# UKU208_cpu.net
KiCad netlist of a schematic drawn in Altium Designer
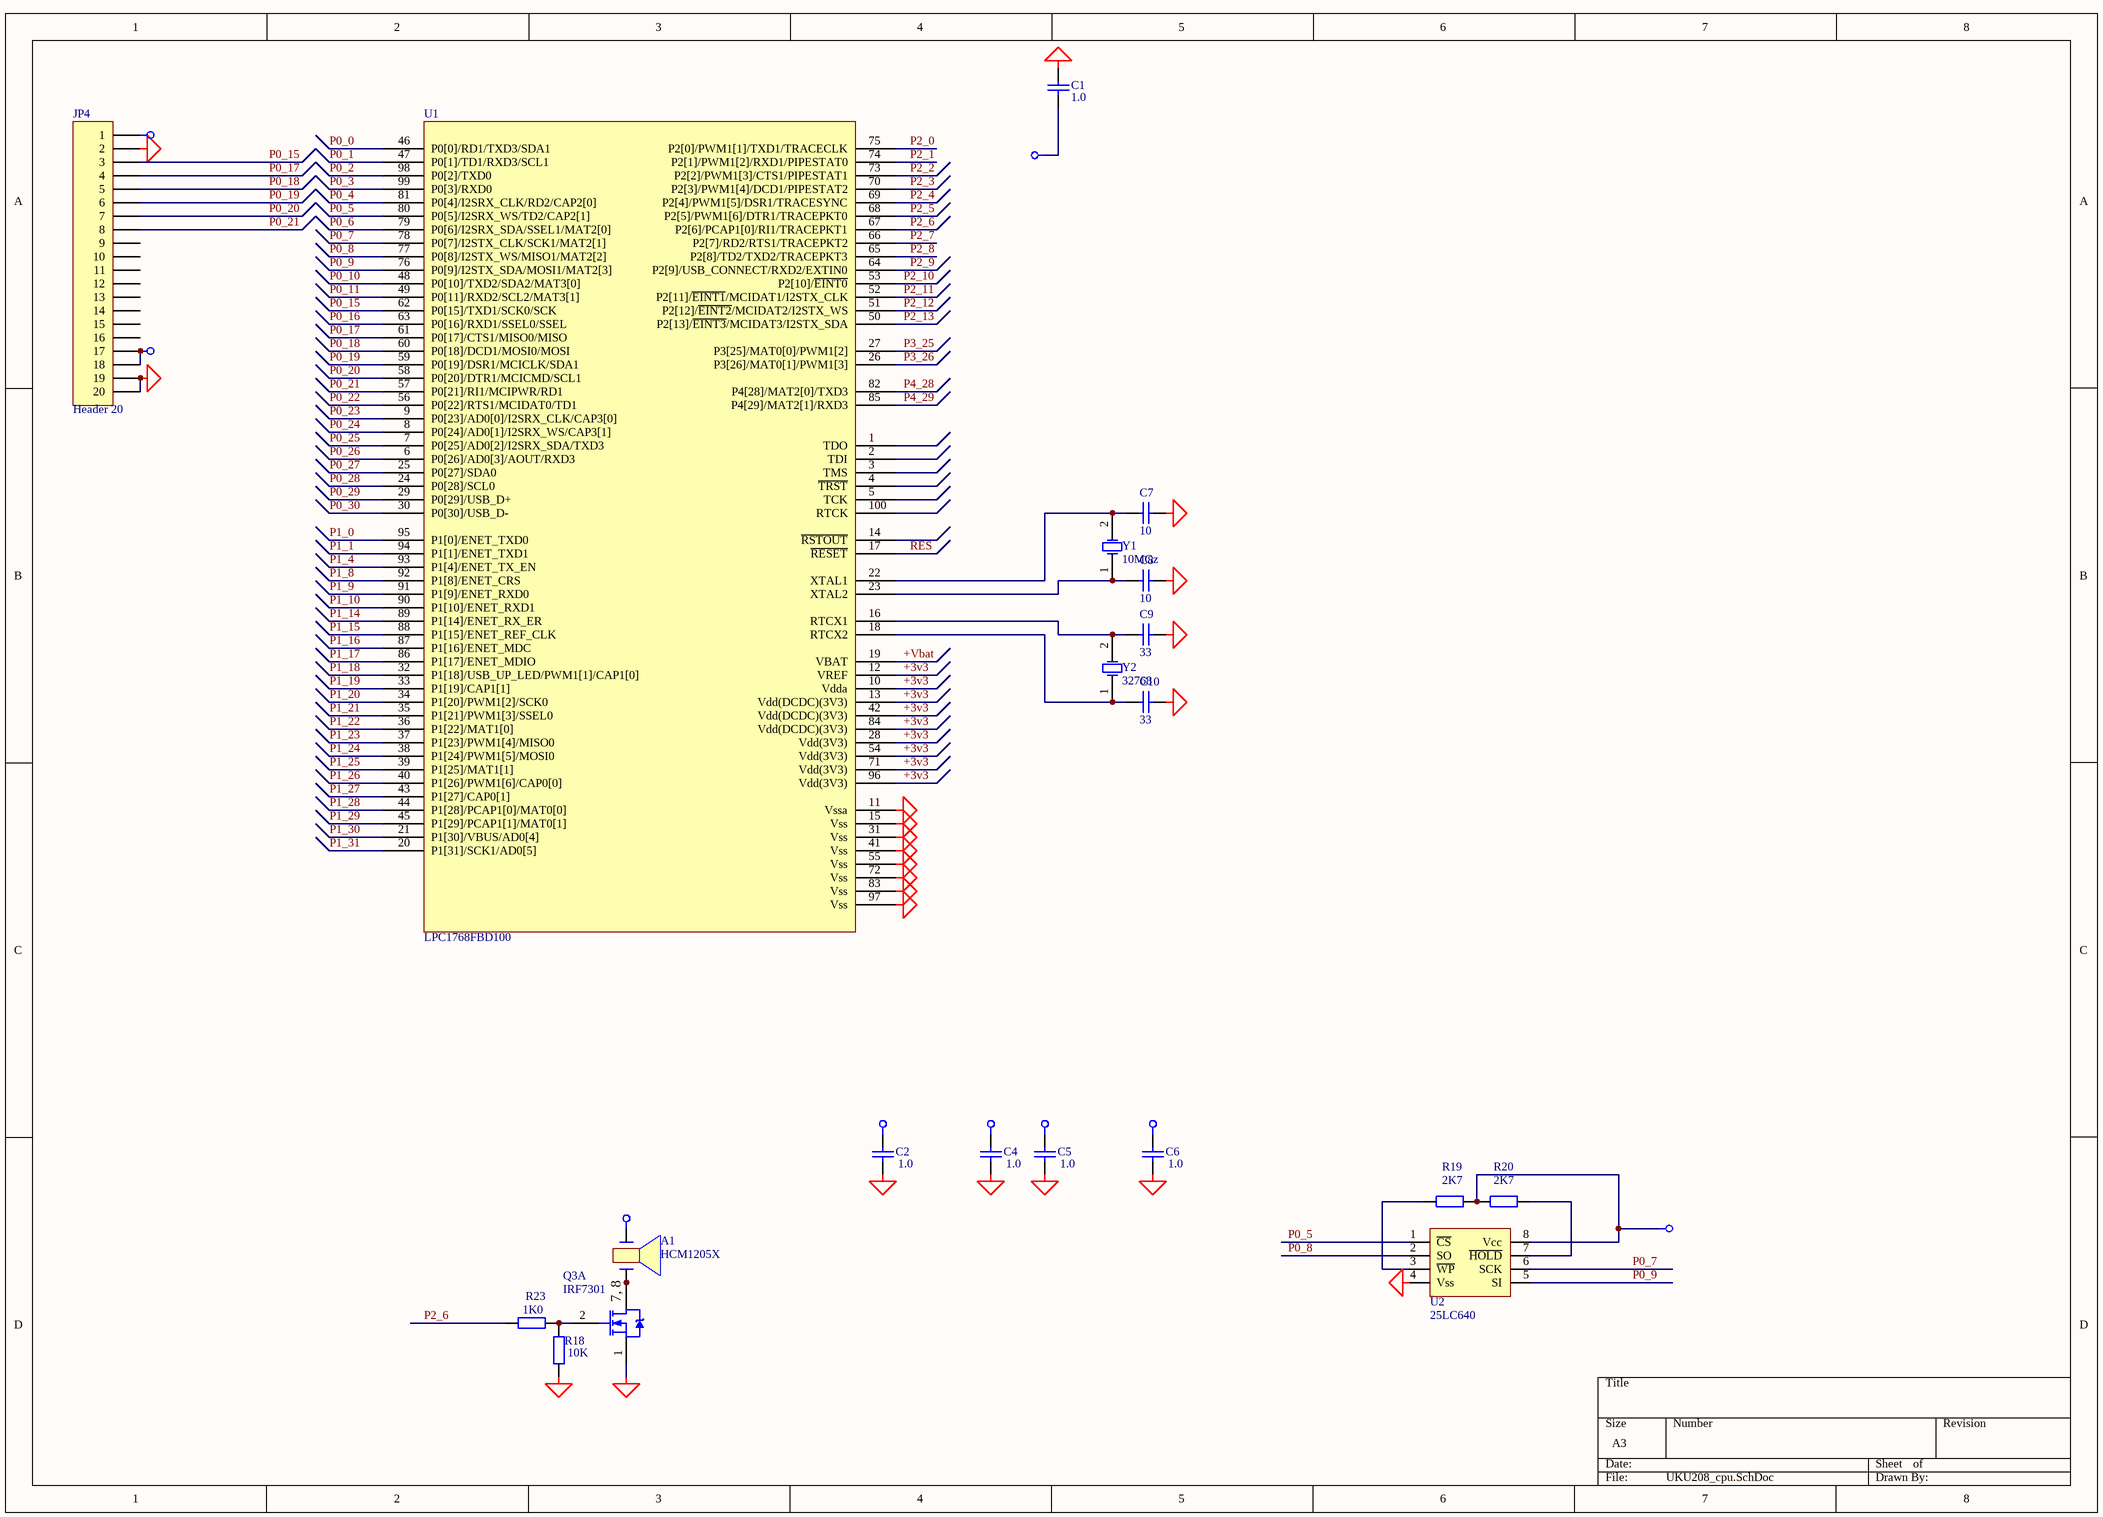
[diagram p0: UKU208_cpu.SchDoc]

(export (version "E")
  (design (tool "Eeschema 10.0.6"))
  (components
    (comp (ref "A1")
      (value "HCM1205X")
      (footprint "zumm")
      (description "Beeper")
      (libsource (lib "PAL") (part "PJEZ0"))
    )
    (comp (ref "C1")
      (value "1.0")
      (footprint "_1206")
      (description "Capacitor")
      (fields (field (name "MANUFACTURER") "Generic Components") (field (name "PUBLISHER") "Altium Limited"))
      (libsource (lib "Miscellaneous Devices") (part "Cap Semi"))
    )
    (comp (ref "C2")
      (value "1.0")
      (footprint "_1206")
      (description "Capacitor")
      (fields (field (name "MANUFACTURER") "Generic Components") (field (name "PUBLISHER") "Altium Limited"))
      (libsource (lib "Miscellaneous Devices") (part "Cap Semi"))
    )
    (comp (ref "C4")
      (value "1.0")
      (footprint "_1206")
      (description "Capacitor")
      (fields (field (name "MANUFACTURER") "Generic Components") (field (name "PUBLISHER") "Altium Limited"))
      (libsource (lib "Miscellaneous Devices") (part "Cap Semi"))
    )
    (comp (ref "C5")
      (value "1.0")
      (footprint "_1206")
      (description "Capacitor")
      (fields (field (name "MANUFACTURER") "Generic Components") (field (name "PUBLISHER") "Altium Limited"))
      (libsource (lib "Miscellaneous Devices") (part "Cap Semi"))
    )
    (comp (ref "C6")
      (value "1.0")
      (footprint "_1206")
      (description "Capacitor")
      (fields (field (name "MANUFACTURER") "Generic Components") (field (name "PUBLISHER") "Altium Limited"))
      (libsource (lib "Miscellaneous Devices") (part "Cap Semi"))
    )
    (comp (ref "C7")
      (value "10")
      (footprint "_1206")
      (description "Capacitor")
      (fields (field (name "MANUFACTURER") "Generic Components") (field (name "PUBLISHER") "Altium Limited"))
      (libsource (lib "Miscellaneous Devices") (part "Cap Semi"))
    )
    (comp (ref "C8")
      (value "10")
      (footprint "_1206")
      (description "Capacitor")
      (fields (field (name "MANUFACTURER") "Generic Components") (field (name "PUBLISHER") "Altium Limited"))
      (libsource (lib "Miscellaneous Devices") (part "Cap Semi"))
    )
    (comp (ref "C9")
      (value "33")
      (footprint "_1206")
      (description "Capacitor (Semiconductor SIM Model)")
      (fields (field (name "MANUFACTURER") "Generic Components") (field (name "PUBLISHER") "Altium Limited"))
      (libsource (lib "Miscellaneous Devices") (part "Cap Semi"))
    )
    (comp (ref "C10")
      (value "33")
      (footprint "_1206")
      (description "Capacitor (Semiconductor SIM Model)")
      (fields (field (name "MANUFACTURER") "Generic Components") (field (name "PUBLISHER") "Altium Limited"))
      (libsource (lib "Miscellaneous Devices") (part "Cap Semi"))
    )
    (comp (ref "JP4")
      (value "Header 20")
      (footprint "XF2M20151A")
      (description "Header, 20-Pin")
      (fields (field (name "MANUFACTURER") "Generic Components") (field (name "PUBLISHER") "Altium Limited"))
      (libsource (lib "Miscellaneous Connectors") (part "Header 20"))
    )
    (comp (ref "Q3")
      (value "IRF7301")
      (footprint "SO-G8/Y2.2")
      (description "FET")
      (fields
        (field (name "MANUFACTURER") "International Rectifier")
        (field (name "PUBLISHER") "Altium Limited")
      )
      (libsource (lib "IR Discrete MOSFET") (part "IRF7301"))
    )
    (comp (ref "R18")
      (value "10K")
      (footprint "_1206")
      (description "Resistor")
      (fields (field (name "MANUFACTURER") "Generic Components") (field (name "PUBLISHER") "Altium Limited"))
      (libsource (lib "Miscellaneous Devices") (part "Res2"))
    )
    (comp (ref "R19")
      (value "2K7")
      (footprint "_1206")
      (description "Resistor")
      (fields (field (name "MANUFACTURER") "Generic Components") (field (name "PUBLISHER") "Altium Limited"))
      (libsource (lib "") (part "Res2_1"))
    )
    (comp (ref "R20")
      (value "2K7")
      (footprint "_1206")
      (description "Resistor")
      (fields (field (name "MANUFACTURER") "Generic Components") (field (name "PUBLISHER") "Altium Limited"))
      (libsource (lib "") (part "Res2_1"))
    )
    (comp (ref "R23")
      (value "1K0")
      (footprint "_1206")
      (description "Resistor")
      (fields (field (name "MANUFACTURER") "Generic Components") (field (name "PUBLISHER") "Altium Limited"))
      (libsource (lib "") (part "Res2_1"))
    )
    (comp (ref "U1")
      (value "LPC1768FBD100")
      (footprint "LPC2368")
      (libsource (lib "PAL") (part "LPC2368FBD100"))
    )
    (comp (ref "U2")
      (value "25LC640")
      (footprint "SO-G8/D5")
      (description "Memory")
      (libsource (lib "PAL") (part "25LC640"))
    )
    (comp (ref "Y1")
      (value "10MGz")
      (footprint "QWARZ1")
      (description "Crystal Oscillator")
      (fields (field (name "MANUFACTURER") "Generic Components") (field (name "PUBLISHER") "Altium Limited"))
      (libsource (lib "Miscellaneous Devices") (part "XTAL"))
    )
    (comp (ref "Y2")
      (value "32768")
      (footprint "QWARZ2")
      (description "Crystal Oscillator")
      (fields (field (name "MANUFACTURER") "Generic Components") (field (name "PUBLISHER") "Altium Limited"))
      (libsource (lib "Miscellaneous Devices") (part "XTAL"))
    )
  )
  (nets
    (net (code "1") (name "+3v3") (class "Default")
      (node (ref "C1") (pin "1") (pinfunction "1_1") (pintype "passive"))
      (node (ref "C5") (pin "2") (pinfunction "2_2") (pintype "passive"))
      (node (ref "JP4") (pin "1") (pinfunction "1_1") (pintype "passive"))
      (node (ref "U1") (pin "10") (pinfunction "Vdda_10") (pintype "passive"))
      (node (ref "U1") (pin "12") (pinfunction "VREF_12") (pintype "passive"))
      (node (ref "U1") (pin "13") (pinfunction "Vdd(DCDC)(3V3)_13") (pintype "passive"))
      (node (ref "U1") (pin "28") (pinfunction "Vdd(3V3)_28") (pintype "passive"))
      (node (ref "U1") (pin "42") (pinfunction "Vdd(DCDC)(3V3)_42") (pintype "passive"))
      (node (ref "U1") (pin "54") (pinfunction "Vdd(3V3)_54") (pintype "passive"))
      (node (ref "U1") (pin "71") (pinfunction "Vdd(3V3)_71") (pintype "passive"))
      (node (ref "U1") (pin "84") (pinfunction "Vdd(DCDC)(3V3)_84") (pintype "passive"))
      (node (ref "U1") (pin "96") (pinfunction "Vdd(3V3)_96") (pintype "passive"))
    )
    (net (code "2") (name "+5v") (class "Default")
      (node (ref "A1") (pin "1") (pinfunction "1_1") (pintype "passive"))
      (node (ref "C2") (pin "2") (pinfunction "2_2") (pintype "passive"))
      (node (ref "C4") (pin "2") (pinfunction "2_2") (pintype "passive"))
      (node (ref "C6") (pin "2") (pinfunction "2_2") (pintype "passive"))
      (node (ref "JP4") (pin "17") (pinfunction "17_17") (pintype "passive"))
      (node (ref "JP4") (pin "18") (pinfunction "18_18") (pintype "passive"))
      (node (ref "R19") (pin "2") (pinfunction "2_2") (pintype "passive"))
      (node (ref "R20") (pin "1") (pinfunction "1_1") (pintype "passive"))
      (node (ref "U2") (pin "8") (pinfunction "Vcc_8") (pintype "passive"))
    )
    (net (code "3") (name "/+Vbat") (class "Default")
      (node (ref "U1") (pin "19") (pinfunction "VBAT_19") (pintype "passive"))
    )
    (net (code "4") (name "/P0_0") (class "Default")
      (node (ref "U1") (pin "46") (pinfunction "P0[0]/RD1/TXD3/SDA1_46") (pintype "passive"))
    )
    (net (code "5") (name "/P0_1") (class "Default")
      (node (ref "U1") (pin "47") (pinfunction "P0[1]/TD1/RXD3/SCL1_47") (pintype "passive"))
    )
    (net (code "6") (name "/P0_2") (class "Default")
      (node (ref "U1") (pin "98") (pinfunction "P0[2]/TXD0_98") (pintype "passive"))
    )
    (net (code "7") (name "/P0_3") (class "Default")
      (node (ref "U1") (pin "99") (pinfunction "P0[3]/RXD0_99") (pintype "passive"))
    )
    (net (code "8") (name "/P0_4") (class "Default")
      (node (ref "U1") (pin "81") (pinfunction "P0[4]/I2SRX_CLK/RD2/CAP2[0]_81") (pintype "passive"))
    )
    (net (code "9") (name "/P0_5") (class "Default")
      (node (ref "U1") (pin "80") (pinfunction "P0[5]/I2SRX_WS/TD2/CAP2[1]_80") (pintype "passive"))
      (node (ref "U2") (pin "1") (pinfunction "~{CS}_1") (pintype "passive"))
    )
    (net (code "10") (name "/P0_6") (class "Default")
      (node (ref "U1") (pin "79") (pinfunction "P0[6]/I2SRX_SDA/SSEL1/MAT2[0]_79") (pintype "passive"))
    )
    (net (code "11") (name "/P0_7") (class "Default")
      (node (ref "U1") (pin "78") (pinfunction "P0[7]/I2STX_CLK/SCK1/MAT2[1]_78") (pintype "passive"))
      (node (ref "U2") (pin "6") (pinfunction "SCK_6") (pintype "passive"))
    )
    (net (code "12") (name "/P0_8") (class "Default")
      (node (ref "U1") (pin "77") (pinfunction "P0[8]/I2STX_WS/MISO1/MAT2[2]_77") (pintype "passive"))
      (node (ref "U2") (pin "2") (pinfunction "SO_2") (pintype "passive"))
    )
    (net (code "13") (name "/P0_9") (class "Default")
      (node (ref "U1") (pin "76") (pinfunction "P0[9]/I2STX_SDA/MOSI1/MAT2[3]_76") (pintype "passive"))
      (node (ref "U2") (pin "5") (pinfunction "SI_5") (pintype "passive"))
    )
    (net (code "14") (name "/P0_10") (class "Default")
      (node (ref "U1") (pin "48") (pinfunction "P0[10]/TXD2/SDA2/MAT3[0]_48") (pintype "passive"))
    )
    (net (code "15") (name "/P0_11") (class "Default")
      (node (ref "U1") (pin "49") (pinfunction "P0[11]/RXD2/SCL2/MAT3[1]_49") (pintype "passive"))
    )
    (net (code "16") (name "/P0_15") (class "Default")
      (node (ref "JP4") (pin "3") (pinfunction "3_3") (pintype "passive"))
      (node (ref "U1") (pin "62") (pinfunction "P0[15]/TXD1/SCK0/SCK_62") (pintype "passive"))
    )
    (net (code "17") (name "/P0_16") (class "Default")
      (node (ref "U1") (pin "63") (pinfunction "P0[16]/RXD1/SSEL0/SSEL_63") (pintype "passive"))
    )
    (net (code "18") (name "/P0_17") (class "Default")
      (node (ref "JP4") (pin "4") (pinfunction "4_4") (pintype "passive"))
      (node (ref "U1") (pin "61") (pinfunction "P0[17]/CTS1/MISO0/MISO_61") (pintype "passive"))
    )
    (net (code "19") (name "/P0_18") (class "Default")
      (node (ref "JP4") (pin "5") (pinfunction "5_5") (pintype "passive"))
      (node (ref "U1") (pin "60") (pinfunction "P0[18]/DCD1/MOSI0/MOSI_60") (pintype "passive"))
    )
    (net (code "20") (name "/P0_19") (class "Default")
      (node (ref "JP4") (pin "6") (pinfunction "6_6") (pintype "passive"))
      (node (ref "U1") (pin "59") (pinfunction "P0[19]/DSR1/MCICLK/SDA1_59") (pintype "passive"))
    )
    (net (code "21") (name "/P0_20") (class "Default")
      (node (ref "JP4") (pin "7") (pinfunction "7_7") (pintype "passive"))
      (node (ref "U1") (pin "58") (pinfunction "P0[20]/DTR1/MCICMD/SCL1_58") (pintype "passive"))
    )
    (net (code "22") (name "/P0_21") (class "Default")
      (node (ref "JP4") (pin "8") (pinfunction "8_8") (pintype "passive"))
      (node (ref "U1") (pin "57") (pinfunction "P0[21]/RI1/MCIPWR/RD1_57") (pintype "passive"))
    )
    (net (code "23") (name "/P0_22") (class "Default")
      (node (ref "U1") (pin "56") (pinfunction "P0[22]/RTS1/MCIDAT0/TD1_56") (pintype "passive"))
    )
    (net (code "24") (name "/P0_23") (class "Default")
      (node (ref "U1") (pin "9") (pinfunction "P0[23]/AD0[0]/I2SRX_CLK/CAP3[0]_9") (pintype "passive"))
    )
    (net (code "25") (name "/P0_24") (class "Default")
      (node (ref "U1") (pin "8") (pinfunction "P0[24]/AD0[1]/I2SRX_WS/CAP3[1]_8") (pintype "passive"))
    )
    (net (code "26") (name "/P0_25") (class "Default")
      (node (ref "U1") (pin "7") (pinfunction "P0[25]/AD0[2]/I2SRX_SDA/TXD3_7") (pintype "passive"))
    )
    (net (code "27") (name "/P0_26") (class "Default")
      (node (ref "U1") (pin "6") (pinfunction "P0[26]/AD0[3]/AOUT/RXD3_6") (pintype "passive"))
    )
    (net (code "28") (name "/P0_27") (class "Default")
      (node (ref "U1") (pin "25") (pinfunction "P0[27]/SDA0_25") (pintype "passive"))
    )
    (net (code "29") (name "/P0_28") (class "Default")
      (node (ref "U1") (pin "24") (pinfunction "P0[28]/SCL0_24") (pintype "passive"))
    )
    (net (code "30") (name "/P0_29") (class "Default")
      (node (ref "U1") (pin "29") (pinfunction "P0[29]/USB_D+_29") (pintype "passive"))
    )
    (net (code "31") (name "/P0_30") (class "Default")
      (node (ref "U1") (pin "30") (pinfunction "P0[30]/USB_D-_30") (pintype "passive"))
    )
    (net (code "32") (name "/P1_0") (class "Default")
      (node (ref "U1") (pin "95") (pinfunction "P1[0]/ENET_TXD0_95") (pintype "passive"))
    )
    (net (code "33") (name "/P1_1") (class "Default")
      (node (ref "U1") (pin "94") (pinfunction "P1[1]/ENET_TXD1_94") (pintype "passive"))
    )
    (net (code "34") (name "/P1_4") (class "Default")
      (node (ref "U1") (pin "93") (pinfunction "P1[4]/ENET_TX_EN_93") (pintype "passive"))
    )
    (net (code "35") (name "/P1_8") (class "Default")
      (node (ref "U1") (pin "92") (pinfunction "P1[8]/ENET_CRS_92") (pintype "passive"))
    )
    (net (code "36") (name "/P1_9") (class "Default")
      (node (ref "U1") (pin "91") (pinfunction "P1[9]/ENET_RXD0_91") (pintype "passive"))
    )
    (net (code "37") (name "/P1_10") (class "Default")
      (node (ref "U1") (pin "90") (pinfunction "P1[10]/ENET_RXD1_90") (pintype "passive"))
    )
    (net (code "38") (name "/P1_14") (class "Default")
      (node (ref "U1") (pin "89") (pinfunction "P1[14]/ENET_RX_ER_89") (pintype "passive"))
    )
    (net (code "39") (name "/P1_15") (class "Default")
      (node (ref "U1") (pin "88") (pinfunction "P1[15]/ENET_REF_CLK_88") (pintype "passive"))
    )
    (net (code "40") (name "/P1_16") (class "Default")
      (node (ref "U1") (pin "87") (pinfunction "P1[16]/ENET_MDC_87") (pintype "passive"))
    )
    (net (code "41") (name "/P1_17") (class "Default")
      (node (ref "U1") (pin "86") (pinfunction "P1[17]/ENET_MDIO_86") (pintype "passive"))
    )
    (net (code "42") (name "/P1_18") (class "Default")
      (node (ref "U1") (pin "32") (pinfunction "P1[18]/USB_UP_LED/PWM1[1]/CAP1[0]_32") (pintype "passive"))
    )
    (net (code "43") (name "/P1_19") (class "Default")
      (node (ref "U1") (pin "33") (pinfunction "P1[19]/CAP1[1]_33") (pintype "passive"))
    )
    (net (code "44") (name "/P1_20") (class "Default")
      (node (ref "U1") (pin "34") (pinfunction "P1[20]/PWM1[2]/SCK0_34") (pintype "passive"))
    )
    (net (code "45") (name "/P1_21") (class "Default")
      (node (ref "U1") (pin "35") (pinfunction "P1[21]/PWM1[3]/SSEL0_35") (pintype "passive"))
    )
    (net (code "46") (name "/P1_22") (class "Default")
      (node (ref "U1") (pin "36") (pinfunction "P1[22]/MAT1[0]_36") (pintype "passive"))
    )
    (net (code "47") (name "/P1_23") (class "Default")
      (node (ref "U1") (pin "37") (pinfunction "P1[23]/PWM1[4]/MISO0_37") (pintype "passive"))
    )
    (net (code "48") (name "/P1_24") (class "Default")
      (node (ref "U1") (pin "38") (pinfunction "P1[24]/PWM1[5]/MOSI0_38") (pintype "passive"))
    )
    (net (code "49") (name "/P1_25") (class "Default")
      (node (ref "U1") (pin "39") (pinfunction "P1[25]/MAT1[1]_39") (pintype "passive"))
    )
    (net (code "50") (name "/P1_26") (class "Default")
      (node (ref "U1") (pin "40") (pinfunction "P1[26]/PWM1[6]/CAP0[0]_40") (pintype "passive"))
    )
    (net (code "51") (name "/P1_27") (class "Default")
      (node (ref "U1") (pin "43") (pinfunction "P1[27]/CAP0[1]_43") (pintype "passive"))
    )
    (net (code "52") (name "/P1_28") (class "Default")
      (node (ref "U1") (pin "44") (pinfunction "P1[28]/PCAP1[0]/MAT0[0]_44") (pintype "passive"))
    )
    (net (code "53") (name "/P1_29") (class "Default")
      (node (ref "U1") (pin "45") (pinfunction "P1[29]/PCAP1[1]/MAT0[1]_45") (pintype "passive"))
    )
    (net (code "54") (name "/P1_30") (class "Default")
      (node (ref "U1") (pin "21") (pinfunction "P1[30]/VBUS/AD0[4]_21") (pintype "passive"))
    )
    (net (code "55") (name "/P1_31") (class "Default")
      (node (ref "U1") (pin "20") (pinfunction "P1[31]/SCK1/AD0[5]_20") (pintype "passive"))
    )
    (net (code "56") (name "/P2_0") (class "Default")
      (node (ref "U1") (pin "75") (pinfunction "P2[0]/PWM1[1]/TXD1/TRACECLK_75") (pintype "passive"))
    )
    (net (code "57") (name "/P2_1") (class "Default")
      (node (ref "U1") (pin "74") (pinfunction "P2[1]/PWM1[2]/RXD1/PIPESTAT0_74") (pintype "passive"))
    )
    (net (code "58") (name "/P2_2") (class "Default")
      (node (ref "U1") (pin "73") (pinfunction "P2[2]/PWM1[3]/CTS1/PIPESTAT1_73") (pintype "passive"))
    )
    (net (code "59") (name "/P2_3") (class "Default")
      (node (ref "U1") (pin "70") (pinfunction "P2[3]/PWM1[4]/DCD1/PIPESTAT2_70") (pintype "passive"))
    )
    (net (code "60") (name "/P2_4") (class "Default")
      (node (ref "U1") (pin "69") (pinfunction "P2[4]/PWM1[5]/DSR1/TRACESYNC_69") (pintype "passive"))
    )
    (net (code "61") (name "/P2_5") (class "Default")
      (node (ref "U1") (pin "68") (pinfunction "P2[5]/PWM1[6]/DTR1/TRACEPKT0_68") (pintype "passive"))
    )
    (net (code "62") (name "/P2_6") (class "Default")
      (node (ref "R23") (pin "1") (pinfunction "1_1") (pintype "passive"))
      (node (ref "U1") (pin "67") (pinfunction "P2[6]/PCAP1[0]/RI1/TRACEPKT1_67") (pintype "passive"))
    )
    (net (code "63") (name "/P2_7") (class "Default")
      (node (ref "U1") (pin "66") (pinfunction "P2[7]/RD2/RTS1/TRACEPKT2_66") (pintype "passive"))
    )
    (net (code "64") (name "/P2_8") (class "Default")
      (node (ref "U1") (pin "65") (pinfunction "P2[8]/TD2/TXD2/TRACEPKT3_65") (pintype "passive"))
    )
    (net (code "65") (name "/P2_9") (class "Default")
      (node (ref "U1") (pin "64") (pinfunction "P2[9]/USB_CONNECT/RXD2/EXTIN0_64") (pintype "passive"))
    )
    (net (code "66") (name "/P2_10") (class "Default")
      (node (ref "U1") (pin "53") (pinfunction "P2[10]/~{EINT0}_53") (pintype "passive"))
    )
    (net (code "67") (name "/P2_11") (class "Default")
      (node (ref "U1") (pin "52") (pinfunction "P2[11]/~{EINT1}/MCIDAT1/I2STX_CLK_52") (pintype "passive"))
    )
    (net (code "68") (name "/P2_12") (class "Default")
      (node (ref "U1") (pin "51") (pinfunction "P2[12]/~{EINT2}/MCIDAT2/I2STX_WS_51") (pintype "passive"))
    )
    (net (code "69") (name "/P2_13") (class "Default")
      (node (ref "U1") (pin "50") (pinfunction "P2[13]/~{EINT3}/MCIDAT3/I2STX_SDA_50") (pintype "passive"))
    )
    (net (code "70") (name "/P3_25") (class "Default")
      (node (ref "U1") (pin "27") (pinfunction "P3[25]/MAT0[0]/PWM1[2]_27") (pintype "passive"))
    )
    (net (code "71") (name "/P3_26") (class "Default")
      (node (ref "U1") (pin "26") (pinfunction "P3[26]/MAT0[1]/PWM1[3]_26") (pintype "passive"))
    )
    (net (code "72") (name "/P4_28") (class "Default")
      (node (ref "U1") (pin "82") (pinfunction "P4[28]/MAT2[0]/TXD3_82") (pintype "passive"))
    )
    (net (code "73") (name "/P4_29") (class "Default")
      (node (ref "U1") (pin "85") (pinfunction "P4[29]/MAT2[1]/RXD3_85") (pintype "passive"))
    )
    (net (code "74") (name "/RES") (class "Default")
      (node (ref "U1") (pin "17") (pinfunction "~{RESET}_17") (pintype "passive"))
    )
    (net (code "75") (name "GND") (class "Default")
      (node (ref "C1") (pin "2") (pinfunction "2_2") (pintype "passive"))
      (node (ref "C10") (pin "1") (pinfunction "1_1") (pintype "passive"))
      (node (ref "C2") (pin "1") (pinfunction "1_1") (pintype "passive"))
      (node (ref "C4") (pin "1") (pinfunction "1_1") (pintype "passive"))
      (node (ref "C5") (pin "1") (pinfunction "1_1") (pintype "passive"))
      (node (ref "C6") (pin "1") (pinfunction "1_1") (pintype "passive"))
      (node (ref "C7") (pin "1") (pinfunction "1_1") (pintype "passive"))
      (node (ref "C8") (pin "1") (pinfunction "1_1") (pintype "passive"))
      (node (ref "C9") (pin "1") (pinfunction "1_1") (pintype "passive"))
      (node (ref "JP4") (pin "19") (pinfunction "19_19") (pintype "passive"))
      (node (ref "JP4") (pin "2") (pinfunction "2_2") (pintype "passive"))
      (node (ref "JP4") (pin "20") (pinfunction "20_20") (pintype "passive"))
      (node (ref "Q3") (pin "1") (pinfunction "S_1") (pintype "passive"))
      (node (ref "R18") (pin "1") (pinfunction "1_1") (pintype "passive"))
      (node (ref "U1") (pin "11") (pinfunction "Vssa_11") (pintype "passive"))
      (node (ref "U1") (pin "15") (pinfunction "Vss_15") (pintype "passive"))
      (node (ref "U1") (pin "31") (pinfunction "Vss_31") (pintype "passive"))
      (node (ref "U1") (pin "41") (pinfunction "Vss_41") (pintype "passive"))
      (node (ref "U1") (pin "55") (pinfunction "Vss_55") (pintype "passive"))
      (node (ref "U1") (pin "72") (pinfunction "Vss_72") (pintype "passive"))
      (node (ref "U1") (pin "83") (pinfunction "Vss_83") (pintype "passive"))
      (node (ref "U1") (pin "97") (pinfunction "Vss_97") (pintype "passive"))
      (node (ref "U2") (pin "4") (pinfunction "Vss_4") (pintype "passive"))
    )
    (net (code "76") (name "Net-(A1-Pad2)") (class "Default")
      (node (ref "A1") (pin "2") (pinfunction "2_2") (pintype "passive"))
      (node (ref "Q3") (pin "7") (pinfunction "D_7") (pintype "passive"))
      (node (ref "Q3") (pin "8") (pinfunction "D_8") (pintype "passive"))
    )
    (net (code "77") (name "Net-(Q3A-G)") (class "Default")
      (node (ref "Q3") (pin "2") (pinfunction "G_2") (pintype "passive"))
      (node (ref "R18") (pin "2") (pinfunction "2_2") (pintype "passive"))
      (node (ref "R23") (pin "2") (pinfunction "2_2") (pintype "passive"))
    )
    (net (code "78") (name "Net-(U1-RTCX1)") (class "Default")
      (node (ref "C9") (pin "2") (pinfunction "2_2") (pintype "passive"))
      (node (ref "U1") (pin "16") (pinfunction "RTCX1_16") (pintype "passive"))
      (node (ref "Y2") (pin "2") (pinfunction "OSC2_2") (pintype "passive"))
    )
    (net (code "79") (name "Net-(U1-RTCX2)") (class "Default")
      (node (ref "C10") (pin "2") (pinfunction "2_2") (pintype "passive"))
      (node (ref "U1") (pin "18") (pinfunction "RTCX2_18") (pintype "passive"))
      (node (ref "Y2") (pin "1") (pinfunction "OSC1_1") (pintype "passive"))
    )
    (net (code "80") (name "Net-(U1-XTAL1)") (class "Default")
      (node (ref "C7") (pin "2") (pinfunction "2_2") (pintype "passive"))
      (node (ref "U1") (pin "22") (pinfunction "XTAL1_22") (pintype "passive"))
      (node (ref "Y1") (pin "2") (pinfunction "OSC2_2") (pintype "passive"))
    )
    (net (code "81") (name "Net-(U1-XTAL2)") (class "Default")
      (node (ref "C8") (pin "2") (pinfunction "2_2") (pintype "passive"))
      (node (ref "U1") (pin "23") (pinfunction "XTAL2_23") (pintype "passive"))
      (node (ref "Y1") (pin "1") (pinfunction "OSC1_1") (pintype "passive"))
    )
    (net (code "82") (name "Net-(U2-~{HOLD})") (class "Default")
      (node (ref "R20") (pin "2") (pinfunction "2_2") (pintype "passive"))
      (node (ref "U2") (pin "7") (pinfunction "~{HOLD}_7") (pintype "passive"))
    )
    (net (code "83") (name "Net-(U2-~{WP})") (class "Default")
      (node (ref "R19") (pin "1") (pinfunction "1_1") (pintype "passive"))
      (node (ref "U2") (pin "3") (pinfunction "~{WP}_3") (pintype "passive"))
    )
    (net (code "84") (name "unconnected-(JP4-Pad9)") (class "Default")
      (node (ref "JP4") (pin "9") (pinfunction "9_9") (pintype "passive"))
    )
    (net (code "85") (name "unconnected-(JP4-Pad10)") (class "Default")
      (node (ref "JP4") (pin "10") (pinfunction "10_10") (pintype "passive"))
    )
    (net (code "86") (name "unconnected-(JP4-Pad11)") (class "Default")
      (node (ref "JP4") (pin "11") (pinfunction "11_11") (pintype "passive"))
    )
    (net (code "87") (name "unconnected-(JP4-Pad12)") (class "Default")
      (node (ref "JP4") (pin "12") (pinfunction "12_12") (pintype "passive"))
    )
    (net (code "88") (name "unconnected-(JP4-Pad13)") (class "Default")
      (node (ref "JP4") (pin "13") (pinfunction "13_13") (pintype "passive"))
    )
    (net (code "89") (name "unconnected-(JP4-Pad14)") (class "Default")
      (node (ref "JP4") (pin "14") (pinfunction "14_14") (pintype "passive"))
    )
    (net (code "90") (name "unconnected-(JP4-Pad15)") (class "Default")
      (node (ref "JP4") (pin "15") (pinfunction "15_15") (pintype "passive"))
    )
    (net (code "91") (name "unconnected-(JP4-Pad16)") (class "Default")
      (node (ref "JP4") (pin "16") (pinfunction "16_16") (pintype "passive"))
    )
    (net (code "92") (name "unconnected-(U1-RTCK-Pad100)") (class "Default")
      (node (ref "U1") (pin "100") (pinfunction "RTCK_100") (pintype "passive"))
    )
    (net (code "93") (name "unconnected-(U1-TCK-Pad5)") (class "Default")
      (node (ref "U1") (pin "5") (pinfunction "TCK_5") (pintype "passive"))
    )
    (net (code "94") (name "unconnected-(U1-TDI-Pad2)") (class "Default")
      (node (ref "U1") (pin "2") (pinfunction "TDI_2") (pintype "passive"))
    )
    (net (code "95") (name "unconnected-(U1-TDO-Pad1)") (class "Default")
      (node (ref "U1") (pin "1") (pinfunction "TDO_1") (pintype "passive"))
    )
    (net (code "96") (name "unconnected-(U1-TMS-Pad3)") (class "Default")
      (node (ref "U1") (pin "3") (pinfunction "TMS_3") (pintype "passive"))
    )
    (net (code "97") (name "unconnected-(U1-~{RSTOUT}-Pad14)") (class "Default")
      (node (ref "U1") (pin "14") (pinfunction "~{RSTOUT}_14") (pintype "passive"))
    )
    (net (code "98") (name "unconnected-(U1-~{TRST}-Pad4)") (class "Default")
      (node (ref "U1") (pin "4") (pinfunction "~{TRST}_4") (pintype "passive"))
    )
  )
)
